# Base_Station_2_1.net
KiCad netlist of a schematic drawn in EAGLE
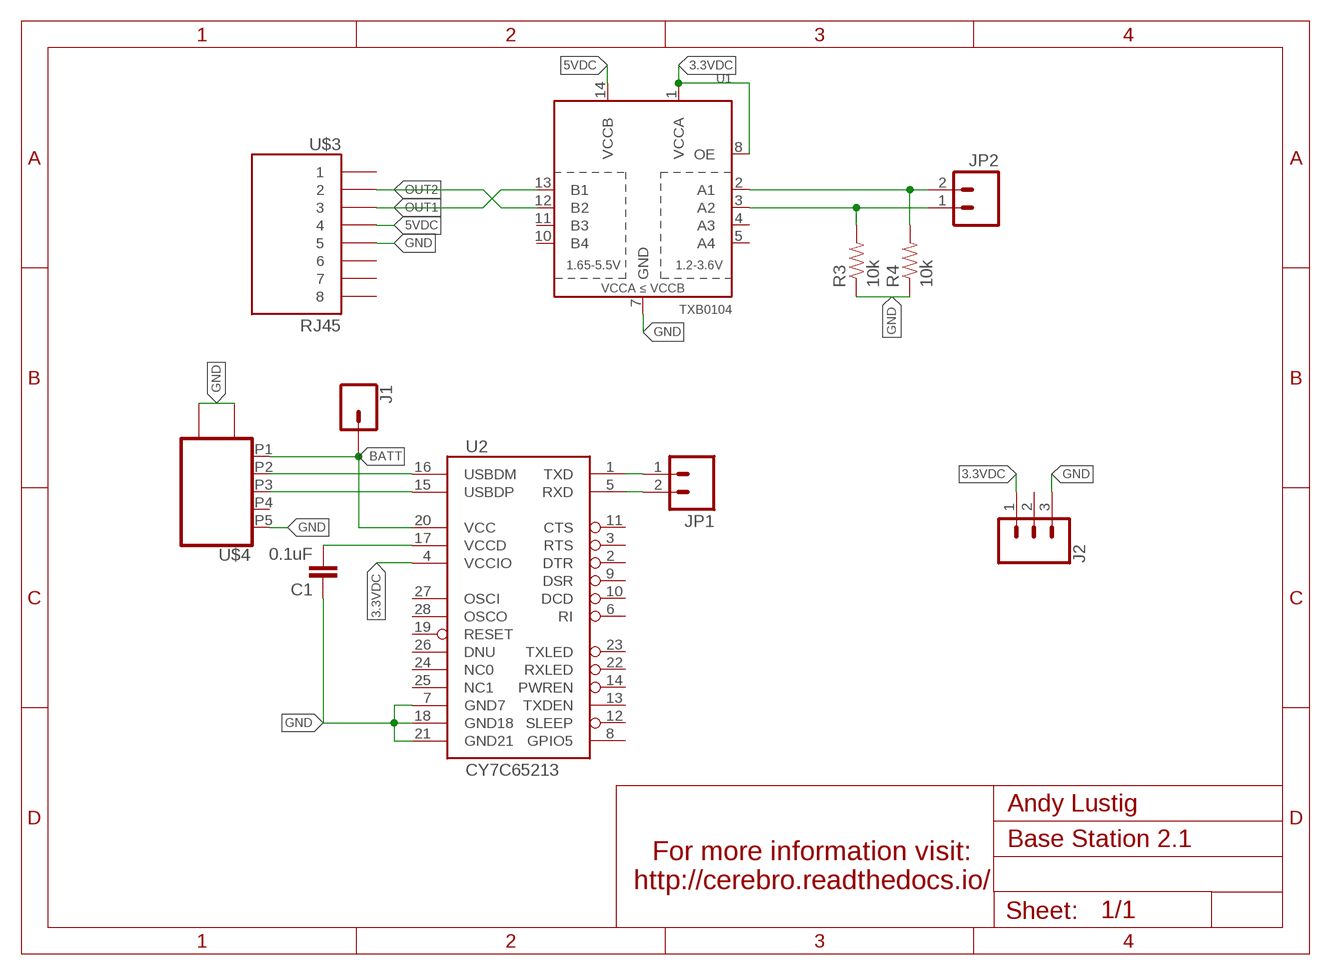
[diagram p0: schematic, sheet 1]

(export (version "E")
  (design (tool "Eeschema 10.0.6"))
  (components
    (comp (ref "C1")
      (value "0.1uF")
      (footprint "eagle-import:0603")
      (libsource (lib "eagle-import") (part "0.1UF-0603-25V-5%"))
    )
    (comp (ref "J1")
      (value "CONN_01PTH_NO_SILK_YES_STOP")
      (footprint "eagle-import:1X01_NO_SILK")
      (libsource (lib "eagle-import") (part "CONN_01PTH_NO_SILK_YES_STOP"))
    )
    (comp (ref "J2")
      (value "CONN_031X03_NO_SILK")
      (footprint "eagle-import:1X03_NO_SILK")
      (libsource (lib "eagle-import") (part "CONN_031X03_NO_SILK"))
    )
    (comp (ref "JP1")
      (value "M021X02_NO_SILK")
      (footprint "eagle-import:1X02_NO_SILK")
      (libsource (lib "eagle-import") (part "M021X02_NO_SILK"))
    )
    (comp (ref "JP2")
      (value "M021X02_NO_SILK")
      (footprint "eagle-import:1X02_NO_SILK")
      (libsource (lib "eagle-import") (part "M021X02_NO_SILK"))
    )
    (comp (ref "R3")
      (value "10k")
      (footprint "eagle-import:0805")
      (libsource (lib "eagle-import") (part "RESISTOR0805-RES"))
    )
    (comp (ref "R4")
      (value "10k")
      (footprint "eagle-import:0805")
      (libsource (lib "eagle-import") (part "RESISTOR0805-RES"))
    )
    (comp (ref "U$3")
      (value "RJ45")
      (footprint "eagle-import:RJ45-8")
      (libsource (lib "eagle-import") (part "RJ45"))
    )
    (comp (ref "U$4")
      (value "USB_MICRO_SOCKET_HORZ_REINFORCED")
      (footprint "eagle-import:USB_HORZ_REINFORCED_MICRO")
      (libsource (lib "eagle-import") (part "USB_MICRO_SOCKET_HORZ_REINFORCED"))
    )
    (comp (ref "U1")
      (value "TXB0104")
      (footprint "eagle-import:TSSOP14")
      (libsource (lib "eagle-import") (part "TXB0104PWR"))
    )
    (comp (ref "U2")
      (value "CY7C65213")
      (footprint "eagle-import:SSOP28DB")
      (libsource (lib "eagle-import") (part "CY7C65213"))
    )
  )
  (nets
    (net (code "1") (name "/NC1") (class "Default")
      (node (ref "U2") (pin "25") (pinfunction "NC1_25") (pintype "power_in"))
    )
    (net (code "2") (name "3.3VDC") (class "Default")
      (node (ref "J2") (pin "1") (pinfunction "1_1") (pintype "passive"))
      (node (ref "U1") (pin "1") (pinfunction "VCCA_1") (pintype "bidirectional"))
      (node (ref "U1") (pin "8") (pinfunction "OE_8") (pintype "bidirectional"))
      (node (ref "U2") (pin "4") (pinfunction "VCCIO_4") (pintype "power_in"))
    )
    (net (code "3") (name "5VDC") (class "Default")
      (node (ref "U$3") (pin "4") (pinfunction "4_4") (pintype "bidirectional"))
      (node (ref "U1") (pin "14") (pinfunction "VCCB_14") (pintype "bidirectional"))
    )
    (net (code "4") (name "BATT") (class "Default")
      (node (ref "J1") (pin "1") (pinfunction "1_1") (pintype "passive"))
      (node (ref "U$4") (pin "P1") (pinfunction "P1_P1") (pintype "bidirectional"))
      (node (ref "U2") (pin "20") (pinfunction "VCC_20") (pintype "power_in"))
    )
    (net (code "5") (name "GND") (class "Default")
      (node (ref "C1") (pin "1") (pinfunction "1_1") (pintype "passive"))
      (node (ref "J2") (pin "3") (pinfunction "3_3") (pintype "passive"))
      (node (ref "R3") (pin "1") (pinfunction "1_1") (pintype "passive"))
      (node (ref "R4") (pin "1") (pinfunction "1_1") (pintype "passive"))
      (node (ref "U$3") (pin "5") (pinfunction "5_5") (pintype "bidirectional"))
      (node (ref "U$4") (pin "G1") (pinfunction "P$1_G1") (pintype "bidirectional"))
      (node (ref "U$4") (pin "G2") (pinfunction "P$1_G2") (pintype "bidirectional"))
      (node (ref "U$4") (pin "P$1") (pinfunction "P$2_P$1") (pintype "bidirectional"))
      (node (ref "U$4") (pin "P$2") (pinfunction "P$2_P$2") (pintype "bidirectional"))
      (node (ref "U$4") (pin "P5") (pinfunction "P5_P5") (pintype "bidirectional"))
      (node (ref "U1") (pin "7") (pinfunction "GND_7") (pintype "bidirectional"))
      (node (ref "U2") (pin "18") (pinfunction "GND18_18") (pintype "power_in"))
      (node (ref "U2") (pin "21") (pinfunction "GND21_21") (pintype "power_in"))
      (node (ref "U2") (pin "7") (pinfunction "GND7_7") (pintype "power_in"))
    )
    (net (code "6") (name "Net-(U1-A1)") (class "Default")
      (node (ref "JP2") (pin "2") (pinfunction "2_2") (pintype "passive"))
      (node (ref "R4") (pin "2") (pinfunction "2_2") (pintype "passive"))
      (node (ref "U1") (pin "2") (pinfunction "A1_2") (pintype "bidirectional"))
    )
    (net (code "7") (name "Net-(U1-A2)") (class "Default")
      (node (ref "JP2") (pin "1") (pinfunction "1_1") (pintype "passive"))
      (node (ref "R3") (pin "2") (pinfunction "2_2") (pintype "passive"))
      (node (ref "U1") (pin "3") (pinfunction "A2_3") (pintype "bidirectional"))
    )
    (net (code "8") (name "Net-(U2-RXD)") (class "Default")
      (node (ref "JP1") (pin "2") (pinfunction "2_2") (pintype "passive"))
      (node (ref "U2") (pin "5") (pinfunction "RXD_5") (pintype "input"))
    )
    (net (code "9") (name "Net-(U2-TXD)") (class "Default")
      (node (ref "JP1") (pin "1") (pinfunction "1_1") (pintype "passive"))
      (node (ref "U2") (pin "1") (pinfunction "TXD_1") (pintype "output"))
    )
    (net (code "10") (name "Net-(U2-USBDM)") (class "Default")
      (node (ref "U$4") (pin "P2") (pinfunction "P2_P2") (pintype "bidirectional"))
      (node (ref "U2") (pin "16") (pinfunction "USBDM_16") (pintype "bidirectional"))
    )
    (net (code "11") (name "Net-(U2-USBDP)") (class "Default")
      (node (ref "U$4") (pin "P3") (pinfunction "P3_P3") (pintype "bidirectional"))
      (node (ref "U2") (pin "15") (pinfunction "USBDP_15") (pintype "bidirectional"))
    )
    (net (code "12") (name "Net-(U2-VCCD)") (class "Default")
      (node (ref "C1") (pin "2") (pinfunction "2_2") (pintype "passive"))
      (node (ref "U2") (pin "17") (pinfunction "VCCD_17") (pintype "output"))
    )
    (net (code "13") (name "OUT1") (class "Default")
      (node (ref "U$3") (pin "3") (pinfunction "3_3") (pintype "bidirectional"))
      (node (ref "U1") (pin "13") (pinfunction "B1_13") (pintype "bidirectional"))
    )
    (net (code "14") (name "OUT2") (class "Default")
      (node (ref "U$3") (pin "2") (pinfunction "2_2") (pintype "bidirectional"))
      (node (ref "U1") (pin "12") (pinfunction "B2_12") (pintype "bidirectional"))
    )
    (net (code "15") (name "unconnected-(J2-Pad2)") (class "Default")
      (node (ref "J2") (pin "2") (pinfunction "2_2") (pintype "passive"))
    )
    (net (code "16") (name "unconnected-(U$3-Pad1)") (class "Default")
      (node (ref "U$3") (pin "1") (pinfunction "1_1") (pintype "bidirectional"))
    )
    (net (code "17") (name "unconnected-(U$3-Pad6)") (class "Default")
      (node (ref "U$3") (pin "6") (pinfunction "6_6") (pintype "bidirectional"))
    )
    (net (code "18") (name "unconnected-(U$3-Pad7)") (class "Default")
      (node (ref "U$3") (pin "7") (pinfunction "7_7") (pintype "bidirectional"))
    )
    (net (code "19") (name "unconnected-(U$3-Pad8)") (class "Default")
      (node (ref "U$3") (pin "8") (pinfunction "8_8") (pintype "bidirectional"))
    )
    (net (code "20") (name "unconnected-(U$4-PadP4)") (class "Default")
      (node (ref "U$4") (pin "P4") (pinfunction "P4_P4") (pintype "bidirectional"))
    )
    (net (code "21") (name "unconnected-(U1-A3-Pad4)") (class "Default")
      (node (ref "U1") (pin "4") (pinfunction "A3_4") (pintype "bidirectional"))
    )
    (net (code "22") (name "unconnected-(U1-A4-Pad5)") (class "Default")
      (node (ref "U1") (pin "5") (pinfunction "A4_5") (pintype "bidirectional"))
    )
    (net (code "23") (name "unconnected-(U1-B3-Pad11)") (class "Default")
      (node (ref "U1") (pin "11") (pinfunction "B3_11") (pintype "bidirectional"))
    )
    (net (code "24") (name "unconnected-(U1-B4-Pad10)") (class "Default")
      (node (ref "U1") (pin "10") (pinfunction "B4_10") (pintype "bidirectional"))
    )
    (net (code "25") (name "unconnected-(U2-CTS-Pad11)") (class "Default")
      (node (ref "U2") (pin "11") (pinfunction "CTS_11") (pintype "input"))
    )
    (net (code "26") (name "unconnected-(U2-DCD-Pad10)") (class "Default")
      (node (ref "U2") (pin "10") (pinfunction "DCD_10") (pintype "input"))
    )
    (net (code "27") (name "unconnected-(U2-DNU-Pad26)") (class "Default")
      (node (ref "U2") (pin "26") (pinfunction "DNU_26") (pintype "input"))
    )
    (net (code "28") (name "unconnected-(U2-DSR-Pad9)") (class "Default")
      (node (ref "U2") (pin "9") (pinfunction "DSR_9") (pintype "input"))
    )
    (net (code "29") (name "unconnected-(U2-DTR-Pad2)") (class "Default")
      (node (ref "U2") (pin "2") (pinfunction "DTR_2") (pintype "output"))
    )
    (net (code "30") (name "unconnected-(U2-GPIO5-Pad8)") (class "Default")
      (node (ref "U2") (pin "8") (pinfunction "GPIO5_8") (pintype "input"))
    )
    (net (code "31") (name "unconnected-(U2-NC0-Pad24)") (class "Default")
      (node (ref "U2") (pin "24") (pinfunction "NC0_24") (pintype "input"))
    )
    (net (code "32") (name "unconnected-(U2-OSCI-Pad27)") (class "Default")
      (node (ref "U2") (pin "27") (pinfunction "OSCI_27") (pintype "input"))
    )
    (net (code "33") (name "unconnected-(U2-OSCO-Pad28)") (class "Default")
      (node (ref "U2") (pin "28") (pinfunction "OSCO_28") (pintype "output"))
    )
    (net (code "34") (name "unconnected-(U2-PWREN-Pad14)") (class "Default")
      (node (ref "U2") (pin "14") (pinfunction "PWREN_14") (pintype "input"))
    )
    (net (code "35") (name "unconnected-(U2-RESET-Pad19)") (class "Default")
      (node (ref "U2") (pin "19") (pinfunction "RESET_19") (pintype "input"))
    )
    (net (code "36") (name "unconnected-(U2-RI-Pad6)") (class "Default")
      (node (ref "U2") (pin "6") (pinfunction "RI_6") (pintype "input"))
    )
    (net (code "37") (name "unconnected-(U2-RTS-Pad3)") (class "Default")
      (node (ref "U2") (pin "3") (pinfunction "RTS_3") (pintype "output"))
    )
    (net (code "38") (name "unconnected-(U2-RXLED-Pad22)") (class "Default")
      (node (ref "U2") (pin "22") (pinfunction "RXLED_22") (pintype "input"))
    )
    (net (code "39") (name "unconnected-(U2-SLEEP-Pad12)") (class "Default")
      (node (ref "U2") (pin "12") (pinfunction "SLEEP_12") (pintype "input"))
    )
    (net (code "40") (name "unconnected-(U2-TXDEN-Pad13)") (class "Default")
      (node (ref "U2") (pin "13") (pinfunction "TXDEN_13") (pintype "input"))
    )
    (net (code "41") (name "unconnected-(U2-TXLED-Pad23)") (class "Default")
      (node (ref "U2") (pin "23") (pinfunction "TXLED_23") (pintype "input"))
    )
  )
)
